# GSMLiftSquare.net
KiCad netlist of a schematic drawn in Altium Designer
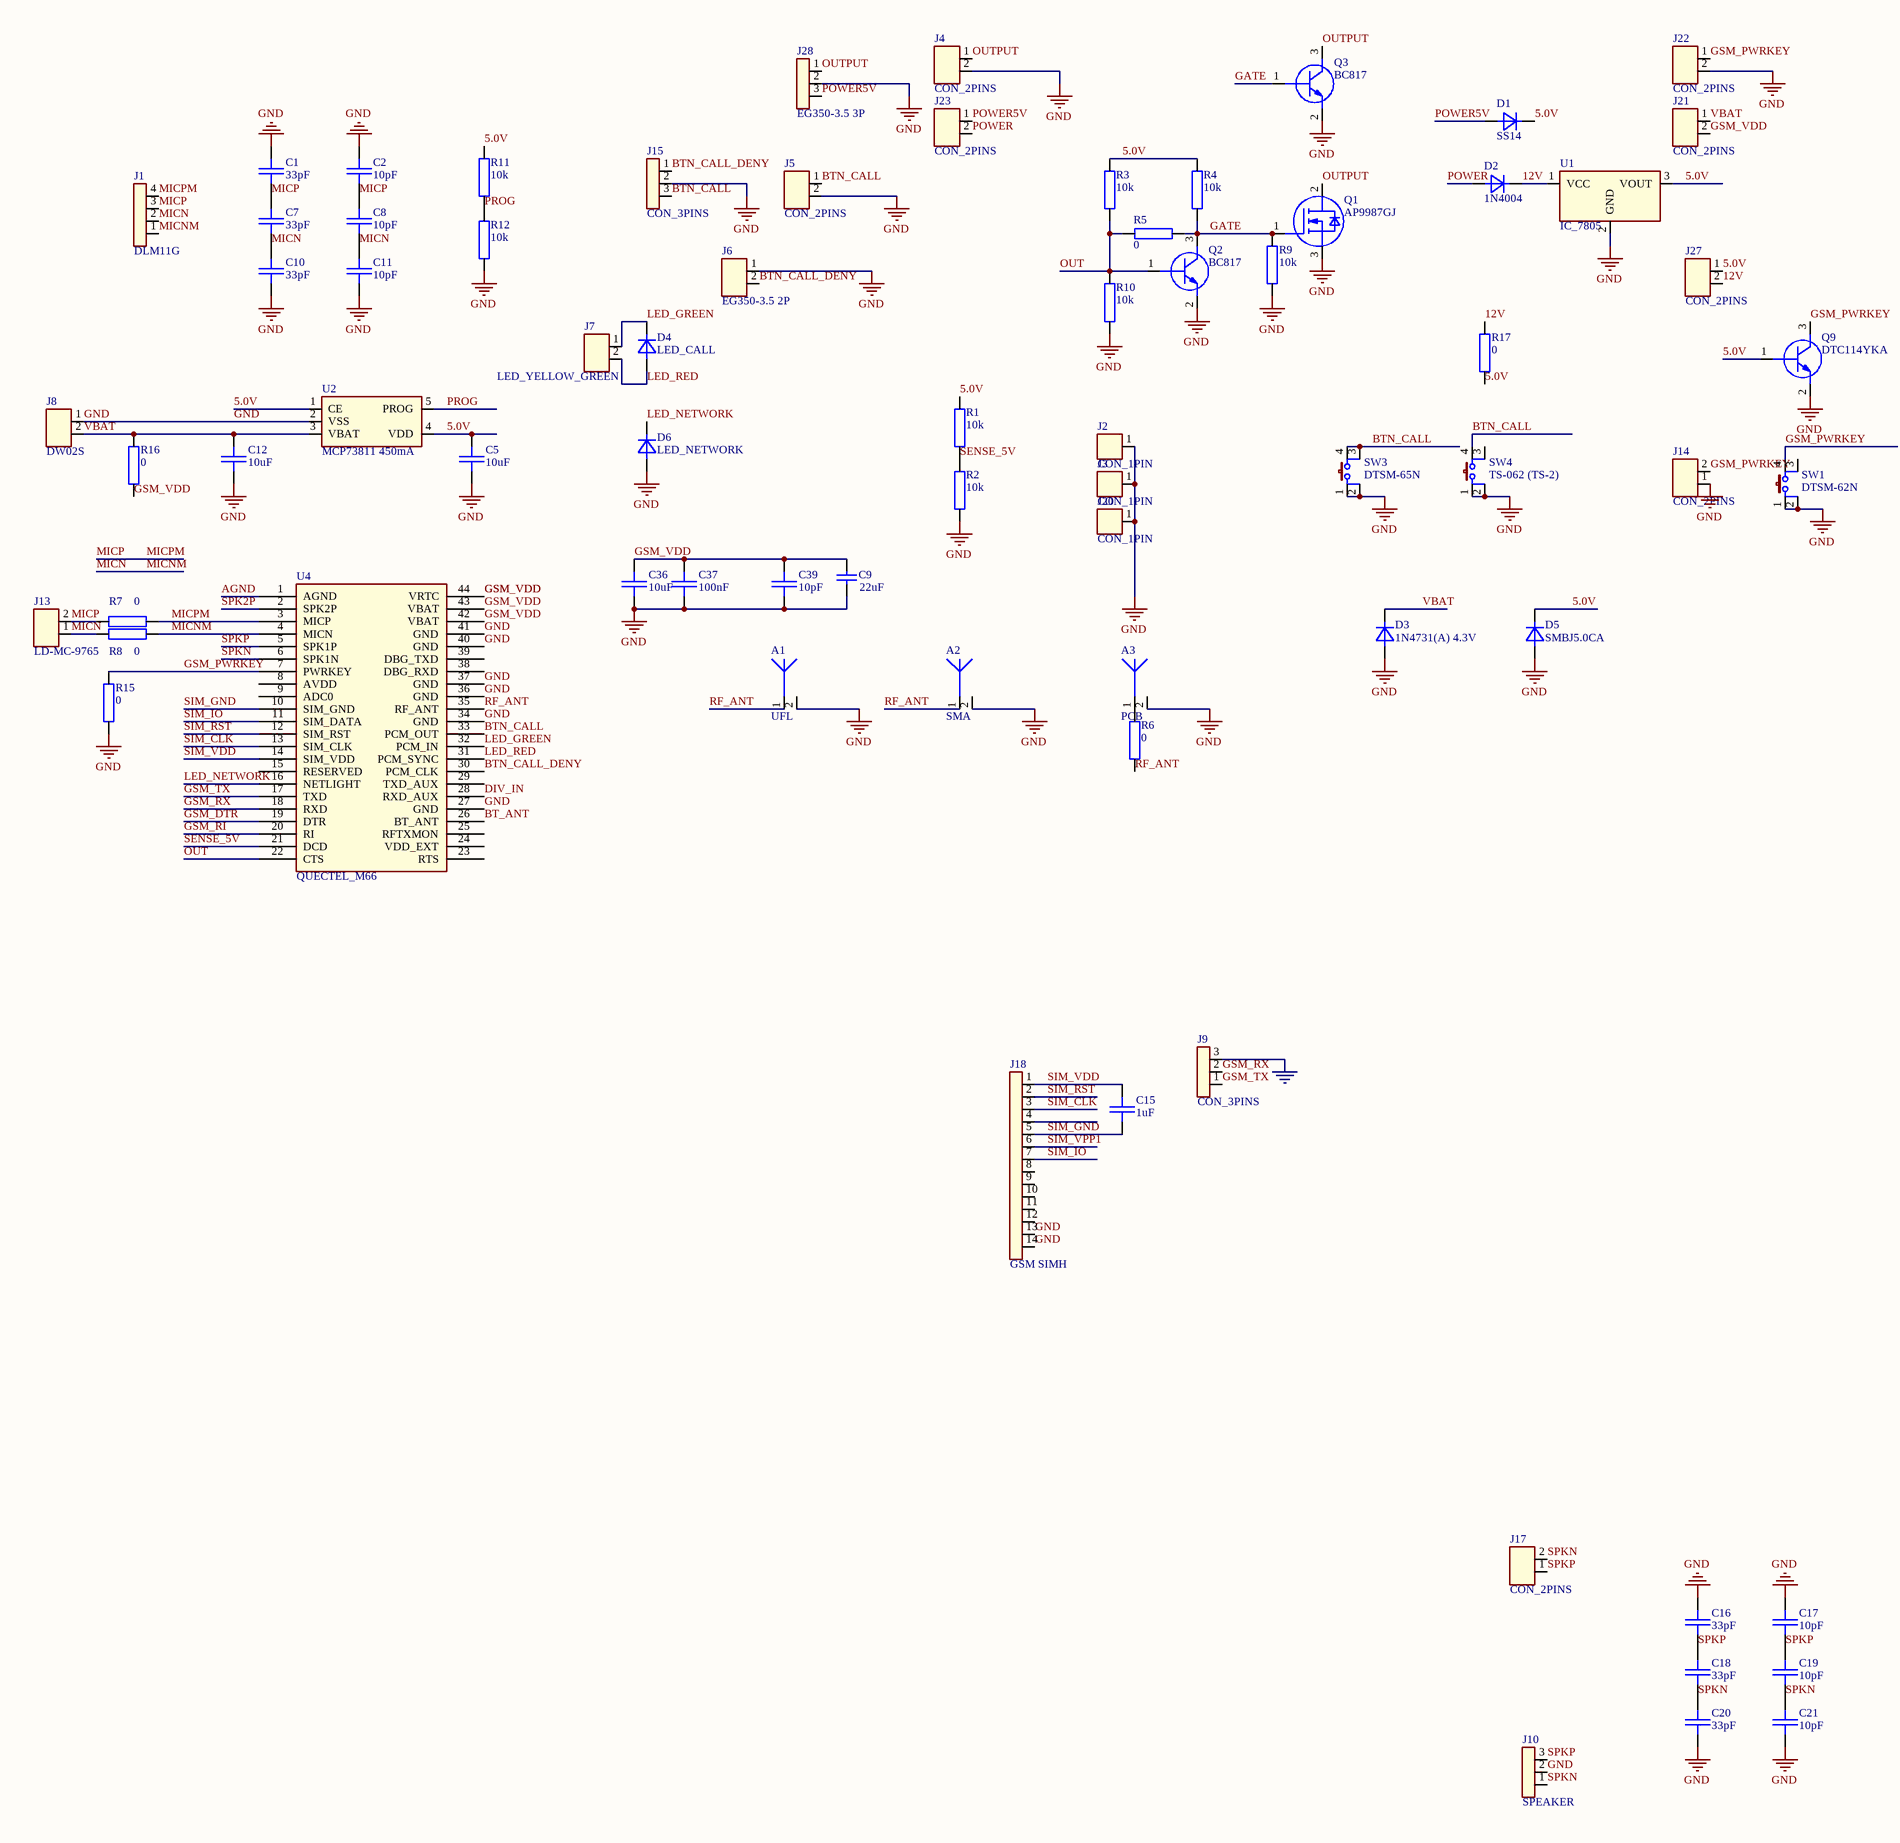
[diagram p0: GSMLiftSquare.SchDoc, left]
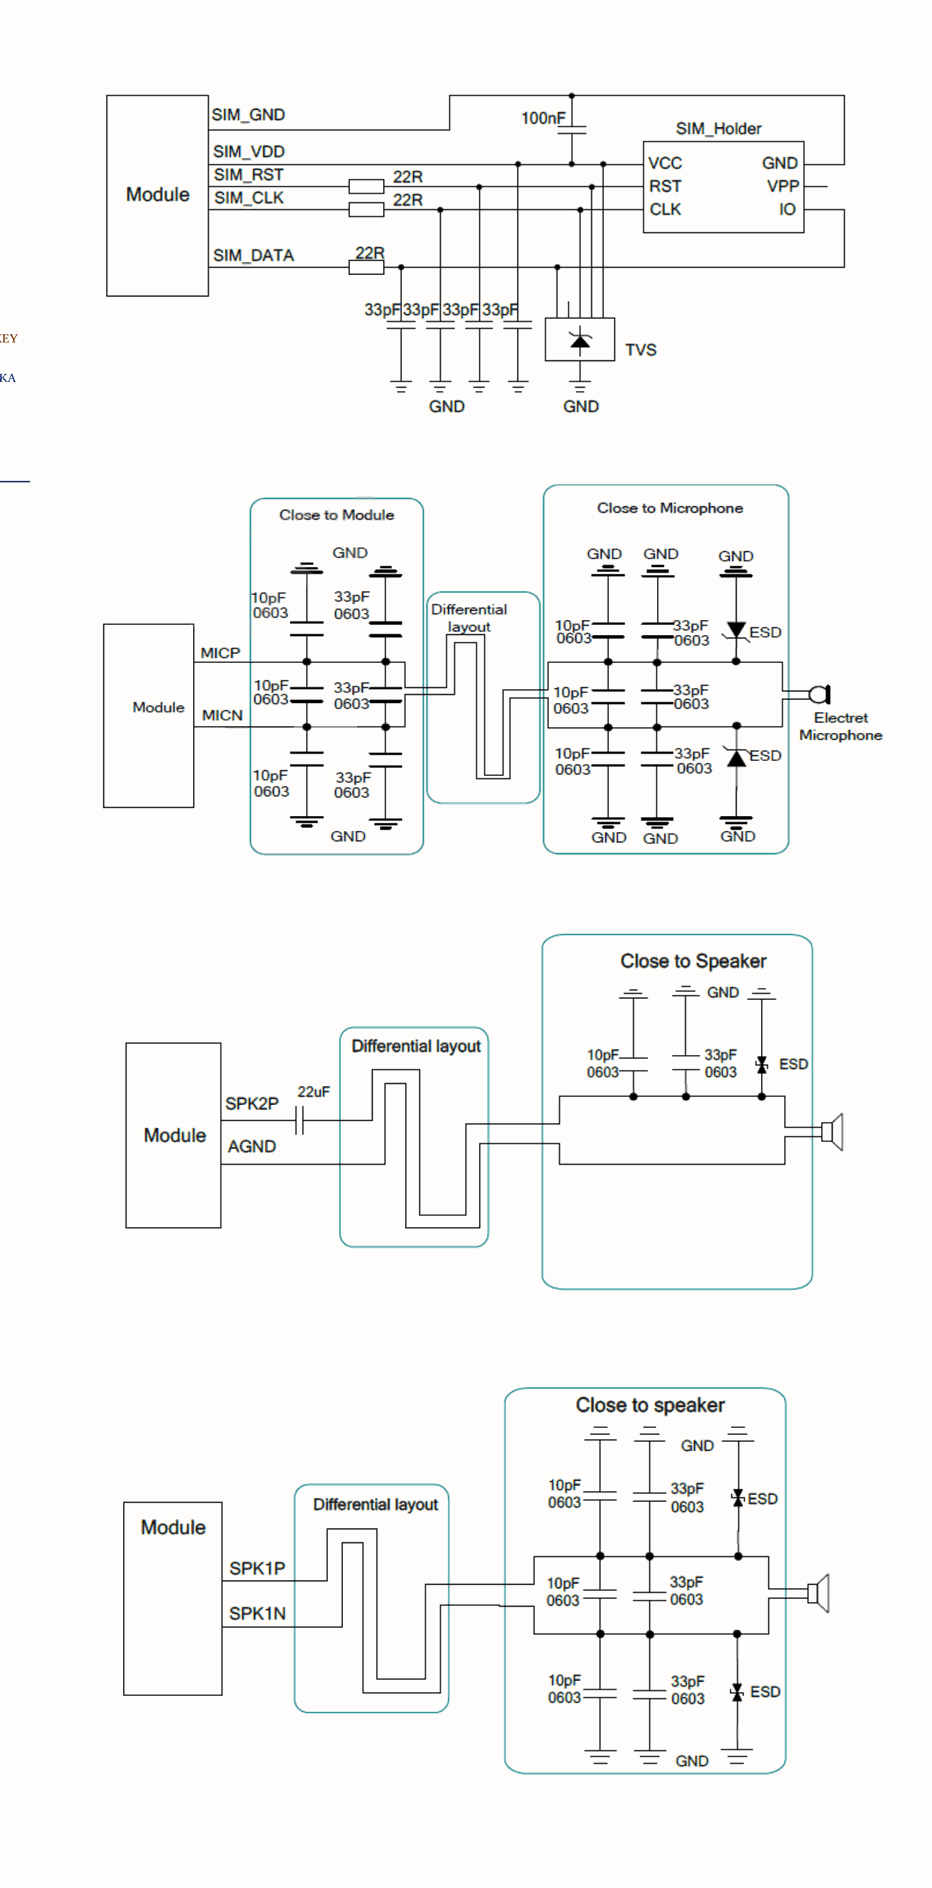
[diagram p1: GSMLiftSquare.SchDoc, right]

(export (version "E")
  (design (tool "Eeschema 10.0.6"))
  (components
    (comp (ref "A1")
      (value "UFL")
      (footprint "SMD_CON_ANTENNA_UFL")
      (libsource (lib "DLV") (part "ANTENNA_2"))
    )
    (comp (ref "A2")
      (value "SMA")
      (footprint "SMD_CON_ANTENNA_SMA_RIGHT_ANGLE")
      (libsource (lib "DLV") (part "ANTENNA_2"))
    )
    (comp (ref "A3")
      (value "PCB")
      (footprint "SMD_CON_ANTENNA_GSM_PCB_1")
      (libsource (lib "DLV") (part "ANTENNA_2"))
    )
    (comp (ref "C1") (value "33pF") (footprint "SMD_0603_CAPC1608X95N") (libsource (lib "DLV") (part "C")))
    (comp (ref "C2") (value "10pF") (footprint "SMD_0603_CAPC1608X95N") (libsource (lib "DLV") (part "C")))
    (comp (ref "C5") (value "10uF") (footprint "SMD_0603_CAPC1608X95N") (libsource (lib "DLV") (part "C")))
    (comp (ref "C7") (value "33pF") (footprint "SMD_0603_CAPC1608X95N") (libsource (lib "DLV") (part "C")))
    (comp (ref "C8") (value "10pF") (footprint "SMD_0603_CAPC1608X95N") (libsource (lib "DLV") (part "C")))
    (comp (ref "C9")
      (value "22uF")
      (footprint "SMD_1210_CAPC3225X279N")
      (description "CL32A227MQVNNNE 220UF 6.3V 20% X5R 1210")
      (fields (field (name "PUBLISHER") "Altium Limited"))
      (libsource (lib "Miscellaneous Devices") (part "Cap Semi"))
    )
    (comp (ref "C10") (value "33pF") (footprint "SMD_0603_CAPC1608X95N") (libsource (lib "DLV") (part "C")))
    (comp (ref "C11") (value "10pF") (footprint "SMD_0603_CAPC1608X95N") (libsource (lib "DLV") (part "C")))
    (comp (ref "C12") (value "10uF") (footprint "SMD_0603_CAPC1608X95N") (libsource (lib "DLV") (part "C")))
    (comp (ref "C15") (value "1uF") (footprint "SMD_0603_CAPC1608X95N") (libsource (lib "DLV") (part "C")))
    (comp (ref "C16") (value "33pF") (footprint "SMD_0603_CAPC1608X95N") (libsource (lib "DLV") (part "C")))
    (comp (ref "C17") (value "10pF") (footprint "SMD_0603_CAPC1608X95N") (libsource (lib "DLV") (part "C")))
    (comp (ref "C18") (value "33pF") (footprint "SMD_0603_CAPC1608X95N") (libsource (lib "DLV") (part "C")))
    (comp (ref "C19") (value "10pF") (footprint "SMD_0603_CAPC1608X95N") (libsource (lib "DLV") (part "C")))
    (comp (ref "C20") (value "33pF") (footprint "SMD_0603_CAPC1608X95N") (libsource (lib "DLV") (part "C")))
    (comp (ref "C21") (value "10pF") (footprint "SMD_0603_CAPC1608X95N") (libsource (lib "DLV") (part "C")))
    (comp (ref "C36") (value "10uF") (footprint "SMD_0805_CAPC2012X95N") (libsource (lib "DLV") (part "C")))
    (comp (ref "C37") (value "100nF") (footprint "SMD_0603_CAPC1608X95N") (libsource (lib "DLV") (part "C")))
    (comp (ref "C39") (value "10pF") (footprint "SMD_0603_CAPC1608X95N") (libsource (lib "DLV") (part "C")))
    (comp (ref "D1")
      (value "SS14")
      (footprint "SMD_DO214AC_SMA")
      (libsource (lib "EPIQ_DND_CIS_Library") (part "D"))
    )
    (comp (ref "D2")
      (value "1N4004")
      (footprint "SMD_DO214AC_SMA")
      (libsource (lib "EPIQ_DND_CIS_Library") (part "D"))
    )
    (comp (ref "D3")
      (value "1N4731(A) 4.3V")
      (footprint "PTH_HDRV02W64P254_1X02")
      (libsource (lib "EPIQ_DND_CIS_Library") (part "D"))
    )
    (comp (ref "D4")
      (value "LED_CALL")
      (footprint "SMD_0805_LED2012X100N")
      (libsource (lib "DLV") (part "D"))
    )
    (comp (ref "D5")
      (value "SMBJ5.0CA")
      (footprint "SMD_DO214AC_SMB")
      (libsource (lib "EPIQ_DND_CIS_Library") (part "D"))
    )
    (comp (ref "D6")
      (value "LED_NETWORK")
      (footprint "SMD_0805_LED2012X100N")
      (libsource (lib "DLV") (part "D"))
    )
    (comp (ref "J1")
      (value "DLM11G")
      (footprint "SMD_COMMON_MODE_CHOKE")
      (libsource (lib "DLV") (part "CON_4PINS"))
    )
    (comp (ref "J2")
      (value "CON_1PIN")
      (footprint "PTH_MOUNT_HOLE")
      (libsource (lib "DLV") (part "CON_1PIN"))
    )
    (comp (ref "J3")
      (value "CON_1PIN")
      (footprint "PTH_MOUNT_HOLE")
      (libsource (lib "DLV") (part "CON_1PIN"))
    )
    (comp (ref "J4")
      (value "CON_2PINS")
      (footprint "PTH_HDRV02W11060P350_1X02")
      (libsource (lib "DLV") (part "CON_2PINS"))
    )
    (comp (ref "J5")
      (value "CON_2PINS")
      (footprint "PTH_HDRV02W11060P500_1X02")
      (libsource (lib "DLV") (part "CON_2PINS"))
    )
    (comp (ref "J6")
      (value "EG350-3.5 2P")
      (footprint "PTH_HDRV02W11060P350_1X02")
      (libsource (lib "DLV") (part "CON_2PINS"))
    )
    (comp (ref "J7")
      (value "LED_YELLOW_GREEN")
      (footprint "PTH_LED-KINGBRIGHT-L-934SGC")
      (libsource (lib "DLV") (part "CON_2PINS"))
    )
    (comp (ref "J8")
      (value "DW02S")
      (footprint "PTH_HDRV02W64P254_1X02_BATTERY")
      (libsource (lib "DLV") (part "CON_2PINS"))
    )
    (comp (ref "J9")
      (value "CON_3PINS")
      (footprint "PTH_HDRV03W64P254_1X03")
      (libsource (lib "") (part "CON_3PINS_1"))
    )
    (comp (ref "J10")
      (value "SPEAKER")
      (footprint "PTH_SPEAKER_MCABS-227-RC")
      (libsource (lib "") (part "CON_3PINS_1"))
    )
    (comp (ref "J13")
      (value "LD-MC-9765")
      (footprint "PTH_MIC_9.6MM_6MM")
      (libsource (lib "") (part "CON_2PINS_1"))
    )
    (comp (ref "J14")
      (value "CON_2PINS")
      (footprint "PTH_HDRV02W64P254_1X02")
      (libsource (lib "") (part "CON_2PINS_1"))
    )
    (comp (ref "J15")
      (value "CON_3PINS")
      (footprint "PTH_HDRV03W64P254_1X03")
      (libsource (lib "DLV") (part "CON_3PINS"))
    )
    (comp (ref "J17")
      (value "CON_2PINS")
      (footprint "PTH_HDRV02W64P254_1X02")
      (libsource (lib "") (part "CON_2PINS_1"))
    )
    (comp (ref "J18")
      (value "GSM SIMH")
      (footprint "SMD_CON-ATTEND_SIM_115B-AAA0-R01")
      (libsource (lib "DLV") (part "CON_14PINS"))
    )
    (comp (ref "J20")
      (value "CON_1PIN")
      (footprint "PTH_MOUNT_HOLE")
      (libsource (lib "DLV") (part "CON_1PIN"))
    )
    (comp (ref "J21")
      (value "CON_2PINS")
      (footprint "PTH_HDRV02W64P254_1X02")
      (libsource (lib "DLV") (part "CON_2PINS"))
    )
    (comp (ref "J22")
      (value "CON_2PINS")
      (footprint "PTH_HDRV02W64P254_1X02")
      (libsource (lib "DLV") (part "CON_2PINS"))
    )
    (comp (ref "J23")
      (value "CON_2PINS")
      (footprint "PTH_HDRV02W11060P350_1X02")
      (libsource (lib "DLV") (part "CON_2PINS"))
    )
    (comp (ref "J27")
      (value "CON_2PINS")
      (footprint "PTH_HDRV02W64P254_1X02")
      (libsource (lib "DLV") (part "CON_2PINS"))
    )
    (comp (ref "J28")
      (value "EG350-3.5 3P")
      (footprint "PTH_HDRV02W11060P350_1X03")
      (libsource (lib "DLV") (part "CON_3PINS"))
    )
    (comp (ref "Q1")
      (value "AP9987GJ")
      (footprint "PTH_TO220AB")
      (libsource (lib "DLV") (part "MOS_N_D1_G1D2S3"))
    )
    (comp (ref "Q2")
      (value "BC817")
      (footprint "SMD_SOT23_SOT95P240X120-3N")
      (libsource (lib "DLV") (part "BJT_NPN_B1E2C3"))
    )
    (comp (ref "Q3")
      (value "BC817")
      (footprint "SMD_SOT23_SOT95P240X120-3N")
      (libsource (lib "DLV") (part "BJT_NPN_B1E2C3"))
    )
    (comp (ref "Q9")
      (value "DTC114YKA")
      (footprint "SMD_SOT23_SOT95P240X120-3N")
      (libsource (lib "DLV") (part "BJT_NPN_B1E2C3"))
    )
    (comp (ref "R1") (value "10k") (footprint "SMD_0603_RESC1608X55N") (libsource (lib "DLV") (part "R")))
    (comp (ref "R2") (value "10k") (footprint "SMD_0603_RESC1608X55N") (libsource (lib "DLV") (part "R")))
    (comp (ref "R3") (value "10k") (footprint "SMD_0603_RESC1608X55N") (libsource (lib "DLV") (part "R")))
    (comp (ref "R4") (value "10k") (footprint "SMD_0603_RESC1608X55N") (libsource (lib "DLV") (part "R")))
    (comp (ref "R5") (value "0") (footprint "SMD_0603_RESC1608X55N") (libsource (lib "DLV") (part "R")))
    (comp (ref "R6") (value "0") (footprint "SMD_0402_RESC1005X37N") (libsource (lib "DLV") (part "R")))
    (comp (ref "R7") (value "0") (footprint "SMD_0402_RESC1005X37N") (libsource (lib "DLV") (part "R")))
    (comp (ref "R8") (value "0") (footprint "SMD_0402_RESC1005X37N") (libsource (lib "DLV") (part "R")))
    (comp (ref "R9") (value "10k") (footprint "SMD_0603_RESC1608X55N") (libsource (lib "DLV") (part "R")))
    (comp (ref "R10") (value "10k") (footprint "SMD_0603_RESC1608X55N") (libsource (lib "DLV") (part "R")))
    (comp (ref "R11") (value "10k") (footprint "SMD_0603_RESC1608X55N") (libsource (lib "DLV") (part "R")))
    (comp (ref "R12") (value "10k") (footprint "SMD_0603_RESC1608X55N") (libsource (lib "DLV") (part "R")))
    (comp (ref "R15") (value "0") (footprint "SMD_0603_RESC1608X55N") (libsource (lib "DLV") (part "R")))
    (comp (ref "R16") (value "0") (footprint "SMD_0603_RESC1608X55N") (libsource (lib "DLV") (part "R")))
    (comp (ref "R17") (value "0") (footprint "SMD_0603_RESC1608X55N") (libsource (lib "DLV") (part "R")))
    (comp (ref "SW1")
      (value "DTSM-62N")
      (footprint "SMD_SW_TACT-64K_5")
      (libsource (lib "DLV") (part "BUTTON_1"))
    )
    (comp (ref "SW3")
      (value "DTSM-65N")
      (footprint "SMD_SW_TACT-64K_5")
      (libsource (lib "DLV") (part "BUTTON_1"))
    )
    (comp (ref "SW4")
      (value "TS-062 (TS-2)")
      (footprint "PTH_SWI_TACT-62K_5")
      (libsource (lib "DLV") (part "BUTTON_1"))
    )
    (comp (ref "U1") (value "IC_7805") (footprint "PTH_TO220AB") (libsource (lib "DLV") (part "IC_7805")))
    (comp (ref "U2")
      (value "MCP73811 450mA")
      (footprint "SMD_SOT26_SOT95P285X140-5N - DLV")
      (description "MCP73812")
      (fields
        (field (name "DB_PART_NUMBER") "PSU000000127")
        (field (name "DB_MANUFACTURER_PART") "ROHM        BD33KA5WF-E2")
        (field (name "DB_APPROVED_BY") "VSN")
      )
      (libsource (lib "DLV") (part "IC_MCP73812"))
    )
    (comp (ref "U4")
      (value "QUECTEL_M66")
      (footprint "SMD_MOD_M66-44N")
      (libsource (lib "DLV") (part "MOD_QUECTEL_M66"))
    )
  )
  (nets
    (net (code "1") (name "/5.0V") (class "Default")
      (node (ref "C5") (pin "1") (pinfunction "1_1") (pintype "passive"))
      (node (ref "D1") (pin "1") (pinfunction "C_1") (pintype "passive"))
      (node (ref "D5") (pin "1") (pinfunction "C_1") (pintype "passive"))
      (node (ref "J27") (pin "1") (pinfunction "1_1") (pintype "passive"))
      (node (ref "Q9") (pin "1") (pinfunction "B_1") (pintype "passive"))
      (node (ref "R1") (pin "1") (pinfunction "1_1") (pintype "passive"))
      (node (ref "R11") (pin "1") (pinfunction "1_1") (pintype "passive"))
      (node (ref "R17") (pin "2") (pinfunction "2_2") (pintype "passive"))
      (node (ref "R3") (pin "1") (pinfunction "1_1") (pintype "passive"))
      (node (ref "R4") (pin "1") (pinfunction "1_1") (pintype "passive"))
      (node (ref "U1") (pin "3") (pinfunction "VOUT_3") (pintype "passive"))
      (node (ref "U2") (pin "1") (pinfunction "CE_1") (pintype "passive"))
      (node (ref "U2") (pin "4") (pinfunction "VDD_4") (pintype "passive"))
    )
    (net (code "2") (name "/12V") (class "Default")
      (node (ref "D2") (pin "1") (pinfunction "C_1") (pintype "passive"))
      (node (ref "J27") (pin "2") (pinfunction "2_2") (pintype "passive"))
      (node (ref "R17") (pin "1") (pinfunction "1_1") (pintype "passive"))
      (node (ref "U1") (pin "1") (pinfunction "VCC_1") (pintype "passive"))
    )
    (net (code "3") (name "/AGND") (class "Default")
      (node (ref "U4") (pin "1") (pinfunction "AGND_1") (pintype "passive"))
    )
    (net (code "4") (name "/BTN_CALL") (class "Default")
      (node (ref "J15") (pin "3") (pinfunction "3_3") (pintype "passive"))
      (node (ref "J5") (pin "1") (pinfunction "1_1") (pintype "passive"))
      (node (ref "SW3") (pin "3") (pinfunction "3_3") (pintype "passive"))
      (node (ref "SW3") (pin "4") (pinfunction "4_4") (pintype "passive"))
      (node (ref "SW4") (pin "4") (pinfunction "4_4") (pintype "passive"))
      (node (ref "U4") (pin "33") (pinfunction "PCM_OUT_33") (pintype "passive"))
    )
    (net (code "5") (name "/BTN_CALL_DENY") (class "Default")
      (node (ref "J15") (pin "1") (pinfunction "1_1") (pintype "passive"))
      (node (ref "J6") (pin "2") (pinfunction "2_2") (pintype "passive"))
      (node (ref "U4") (pin "30") (pinfunction "PCM_CLK_30") (pintype "passive"))
    )
    (net (code "6") (name "/BT_ANT") (class "Default")
      (node (ref "U4") (pin "26") (pinfunction "BT_ANT_26") (pintype "passive"))
    )
    (net (code "7") (name "/DIV_IN") (class "Default")
      (node (ref "U4") (pin "28") (pinfunction "RXD_AUX_28") (pintype "passive"))
    )
    (net (code "8") (name "/GATE") (class "Default")
      (node (ref "Q1") (pin "1") (pinfunction "G_1") (pintype "passive"))
      (node (ref "Q2") (pin "3") (pinfunction "C_3") (pintype "passive"))
      (node (ref "Q3") (pin "1") (pinfunction "B_1") (pintype "passive"))
      (node (ref "R4") (pin "2") (pinfunction "2_2") (pintype "passive"))
      (node (ref "R5") (pin "2") (pinfunction "2_2") (pintype "passive"))
      (node (ref "R9") (pin "1") (pinfunction "1_1") (pintype "passive"))
    )
    (net (code "9") (name "/GSM_DTR") (class "Default")
      (node (ref "U4") (pin "19") (pinfunction "DTR_19") (pintype "passive"))
    )
    (net (code "10") (name "/GSM_PWRKEY") (class "Default")
      (node (ref "J14") (pin "2") (pinfunction "2_2") (pintype "passive"))
      (node (ref "J22") (pin "1") (pinfunction "1_1") (pintype "passive"))
      (node (ref "Q9") (pin "3") (pinfunction "C_3") (pintype "passive"))
      (node (ref "R15") (pin "1") (pinfunction "1_1") (pintype "passive"))
      (node (ref "SW1") (pin "4") (pinfunction "4_4") (pintype "passive"))
      (node (ref "U4") (pin "7") (pinfunction "PWRKEY_7") (pintype "passive"))
    )
    (net (code "11") (name "/GSM_RI") (class "Default")
      (node (ref "U4") (pin "20") (pinfunction "RI_20") (pintype "passive"))
    )
    (net (code "12") (name "/GSM_RX") (class "Default")
      (node (ref "J9") (pin "2") (pinfunction "2_2") (pintype "passive"))
      (node (ref "U4") (pin "18") (pinfunction "RXD_18") (pintype "passive"))
    )
    (net (code "13") (name "/GSM_TX") (class "Default")
      (node (ref "J9") (pin "1") (pinfunction "1_1") (pintype "passive"))
      (node (ref "U4") (pin "17") (pinfunction "TXD_17") (pintype "passive"))
    )
    (net (code "14") (name "/GSM_VDD") (class "Default")
      (node (ref "C36") (pin "1") (pinfunction "1_1") (pintype "passive"))
      (node (ref "C37") (pin "1") (pinfunction "1_1") (pintype "passive"))
      (node (ref "C39") (pin "1") (pinfunction "1_1") (pintype "passive"))
      (node (ref "C9") (pin "1") (pinfunction "1_1") (pintype "passive"))
      (node (ref "J21") (pin "2") (pinfunction "2_2") (pintype "passive"))
      (node (ref "R16") (pin "1") (pinfunction "1_1") (pintype "passive"))
      (node (ref "U4") (pin "42") (pinfunction "VBAT_42") (pintype "passive"))
      (node (ref "U4") (pin "43") (pinfunction "VBAT_43") (pintype "passive"))
      (node (ref "U4") (pin "44") (pinfunction "VRTC_44") (pintype "passive"))
    )
    (net (code "15") (name "/LED_GREEN") (class "Default")
      (node (ref "D4") (pin "1") (pinfunction "C_1") (pintype "passive"))
      (node (ref "J7") (pin "1") (pinfunction "1_1") (pintype "passive"))
      (node (ref "U4") (pin "32") (pinfunction "PCM_IN_32") (pintype "passive"))
    )
    (net (code "16") (name "/LED_NETWORK") (class "Default")
      (node (ref "D6") (pin "1") (pinfunction "C_1") (pintype "passive"))
      (node (ref "U4") (pin "16") (pinfunction "NETLIGHT_16") (pintype "passive"))
    )
    (net (code "17") (name "/LED_RED") (class "Default")
      (node (ref "D4") (pin "2") (pinfunction "A_2") (pintype "passive"))
      (node (ref "J7") (pin "2") (pinfunction "2_2") (pintype "passive"))
      (node (ref "U4") (pin "31") (pinfunction "PCM_SYNC_31") (pintype "passive"))
    )
    (net (code "18") (name "/MICN") (class "Default")
      (node (ref "C10") (pin "1") (pinfunction "1_1") (pintype "passive"))
      (node (ref "C11") (pin "1") (pinfunction "1_1") (pintype "passive"))
      (node (ref "C7") (pin "2") (pinfunction "2_2") (pintype "passive"))
      (node (ref "C8") (pin "2") (pinfunction "2_2") (pintype "passive"))
      (node (ref "J1") (pin "1") (pinfunction "1_1") (pintype "passive"))
      (node (ref "J1") (pin "2") (pinfunction "2_2") (pintype "passive"))
      (node (ref "J13") (pin "1") (pinfunction "1_1") (pintype "passive"))
      (node (ref "R8") (pin "1") (pinfunction "1_1") (pintype "passive"))
      (node (ref "R8") (pin "2") (pinfunction "2_2") (pintype "passive"))
      (node (ref "U4") (pin "4") (pinfunction "MICN_4") (pintype "passive"))
    )
    (net (code "19") (name "/MICP") (class "Default")
      (node (ref "C1") (pin "2") (pinfunction "2_2") (pintype "passive"))
      (node (ref "C2") (pin "2") (pinfunction "2_2") (pintype "passive"))
      (node (ref "C7") (pin "1") (pinfunction "1_1") (pintype "passive"))
      (node (ref "C8") (pin "1") (pinfunction "1_1") (pintype "passive"))
      (node (ref "J1") (pin "3") (pinfunction "3_3") (pintype "passive"))
      (node (ref "J1") (pin "4") (pinfunction "4_4") (pintype "passive"))
      (node (ref "J13") (pin "2") (pinfunction "2_2") (pintype "passive"))
      (node (ref "R7") (pin "1") (pinfunction "1_1") (pintype "passive"))
      (node (ref "R7") (pin "2") (pinfunction "2_2") (pintype "passive"))
      (node (ref "U4") (pin "3") (pinfunction "MICP_3") (pintype "passive"))
    )
    (net (code "20") (name "/OUT") (class "Default")
      (node (ref "Q2") (pin "1") (pinfunction "B_1") (pintype "passive"))
      (node (ref "R10") (pin "1") (pinfunction "1_1") (pintype "passive"))
      (node (ref "R3") (pin "2") (pinfunction "2_2") (pintype "passive"))
      (node (ref "R5") (pin "1") (pinfunction "1_1") (pintype "passive"))
      (node (ref "U4") (pin "22") (pinfunction "CTS_22") (pintype "passive"))
    )
    (net (code "21") (name "/OUTPUT") (class "Default")
      (node (ref "J28") (pin "1") (pinfunction "1_1") (pintype "passive"))
      (node (ref "J4") (pin "1") (pinfunction "1_1") (pintype "passive"))
      (node (ref "Q1") (pin "2") (pinfunction "D_2") (pintype "passive"))
      (node (ref "Q3") (pin "3") (pinfunction "C_3") (pintype "passive"))
    )
    (net (code "22") (name "/POWER") (class "Default")
      (node (ref "D2") (pin "2") (pinfunction "A_2") (pintype "passive"))
      (node (ref "J23") (pin "2") (pinfunction "2_2") (pintype "passive"))
    )
    (net (code "23") (name "/POWER5V") (class "Default")
      (node (ref "D1") (pin "2") (pinfunction "A_2") (pintype "passive"))
      (node (ref "J23") (pin "1") (pinfunction "1_1") (pintype "passive"))
      (node (ref "J28") (pin "3") (pinfunction "3_3") (pintype "passive"))
    )
    (net (code "24") (name "/PROG") (class "Default")
      (node (ref "R11") (pin "2") (pinfunction "2_2") (pintype "passive"))
      (node (ref "R12") (pin "1") (pinfunction "1_1") (pintype "passive"))
      (node (ref "U2") (pin "5") (pinfunction "PROG_5") (pintype "passive"))
    )
    (net (code "25") (name "/RF_ANT") (class "Default")
      (node (ref "A1") (pin "1") (pinfunction "1_1") (pintype "passive"))
      (node (ref "A2") (pin "1") (pinfunction "1_1") (pintype "passive"))
      (node (ref "R6") (pin "2") (pinfunction "2_2") (pintype "passive"))
      (node (ref "U4") (pin "35") (pinfunction "RF_ANT_35") (pintype "passive"))
    )
    (net (code "26") (name "/SENSE_5V") (class "Default")
      (node (ref "R1") (pin "2") (pinfunction "2_2") (pintype "passive"))
      (node (ref "R2") (pin "1") (pinfunction "1_1") (pintype "passive"))
      (node (ref "U4") (pin "21") (pinfunction "DCD_21") (pintype "passive"))
    )
    (net (code "27") (name "/SIM_CLK") (class "Default")
      (node (ref "J18") (pin "3") (pinfunction "3_3") (pintype "passive"))
      (node (ref "U4") (pin "13") (pinfunction "SIM_CLK_13") (pintype "passive"))
    )
    (net (code "28") (name "/SIM_GND") (class "Default")
      (node (ref "C15") (pin "2") (pinfunction "2_2") (pintype "passive"))
      (node (ref "J18") (pin "5") (pinfunction "5_5") (pintype "passive"))
      (node (ref "U4") (pin "10") (pinfunction "SIM_GND_10") (pintype "passive"))
    )
    (net (code "29") (name "/SIM_IO") (class "Default")
      (node (ref "J18") (pin "7") (pinfunction "7_7") (pintype "passive"))
      (node (ref "U4") (pin "11") (pinfunction "SIM_DATA_11") (pintype "passive"))
    )
    (net (code "30") (name "/SIM_RST") (class "Default")
      (node (ref "J18") (pin "2") (pinfunction "2_2") (pintype "passive"))
      (node (ref "U4") (pin "12") (pinfunction "SIM_RST_12") (pintype "passive"))
    )
    (net (code "31") (name "/SIM_VDD") (class "Default")
      (node (ref "C15") (pin "1") (pinfunction "1_1") (pintype "passive"))
      (node (ref "J18") (pin "1") (pinfunction "1_1") (pintype "passive"))
      (node (ref "U4") (pin "14") (pinfunction "SIM_VDD_14") (pintype "passive"))
    )
    (net (code "32") (name "/SIM_VPP1") (class "Default")
      (node (ref "J18") (pin "6") (pinfunction "6_6") (pintype "passive"))
    )
    (net (code "33") (name "/SPK2P") (class "Default")
      (node (ref "U4") (pin "2") (pinfunction "SPK2P_2") (pintype "passive"))
    )
    (net (code "34") (name "/SPKN") (class "Default")
      (node (ref "C18") (pin "2") (pinfunction "2_2") (pintype "passive"))
      (node (ref "C19") (pin "2") (pinfunction "2_2") (pintype "passive"))
      (node (ref "C20") (pin "1") (pinfunction "1_1") (pintype "passive"))
      (node (ref "C21") (pin "1") (pinfunction "1_1") (pintype "passive"))
      (node (ref "J10") (pin "1") (pinfunction "1_1") (pintype "passive"))
      (node (ref "J17") (pin "2") (pinfunction "2_2") (pintype "passive"))
      (node (ref "U4") (pin "6") (pinfunction "SPK1N_6") (pintype "passive"))
    )
    (net (code "35") (name "/SPKP") (class "Default")
      (node (ref "C16") (pin "2") (pinfunction "2_2") (pintype "passive"))
      (node (ref "C17") (pin "2") (pinfunction "2_2") (pintype "passive"))
      (node (ref "C18") (pin "1") (pinfunction "1_1") (pintype "passive"))
      (node (ref "C19") (pin "1") (pinfunction "1_1") (pintype "passive"))
      (node (ref "J10") (pin "3") (pinfunction "3_3") (pintype "passive"))
      (node (ref "J17") (pin "1") (pinfunction "1_1") (pintype "passive"))
      (node (ref "U4") (pin "5") (pinfunction "SPK1P_5") (pintype "passive"))
    )
    (net (code "36") (name "/VBAT") (class "Default")
      (node (ref "C12") (pin "1") (pinfunction "1_1") (pintype "passive"))
      (node (ref "D3") (pin "1") (pinfunction "C_1") (pintype "passive"))
      (node (ref "J21") (pin "1") (pinfunction "1_1") (pintype "passive"))
      (node (ref "J8") (pin "2") (pinfunction "2_2") (pintype "passive"))
      (node (ref "R16") (pin "2") (pinfunction "2_2") (pintype "passive"))
      (node (ref "U2") (pin "3") (pinfunction "VBAT_3") (pintype "passive"))
    )
    (net (code "37") (name "GND") (class "Default")
      (node (ref "A1") (pin "2") (pinfunction "2_2") (pintype "passive"))
      (node (ref "A2") (pin "2") (pinfunction "2_2") (pintype "passive"))
      (node (ref "A3") (pin "2") (pinfunction "2_2") (pintype "passive"))
      (node (ref "C1") (pin "1") (pinfunction "1_1") (pintype "passive"))
      (node (ref "C10") (pin "2") (pinfunction "2_2") (pintype "passive"))
      (node (ref "C11") (pin "2") (pinfunction "2_2") (pintype "passive"))
      (node (ref "C12") (pin "2") (pinfunction "2_2") (pintype "passive"))
      (node (ref "C16") (pin "1") (pinfunction "1_1") (pintype "passive"))
      (node (ref "C17") (pin "1") (pinfunction "1_1") (pintype "passive"))
      (node (ref "C2") (pin "1") (pinfunction "1_1") (pintype "passive"))
      (node (ref "C20") (pin "2") (pinfunction "2_2") (pintype "passive"))
      (node (ref "C21") (pin "2") (pinfunction "2_2") (pintype "passive"))
      (node (ref "C36") (pin "2") (pinfunction "2_2") (pintype "passive"))
      (node (ref "C37") (pin "2") (pinfunction "2_2") (pintype "passive"))
      (node (ref "C39") (pin "2") (pinfunction "2_2") (pintype "passive"))
      (node (ref "C5") (pin "2") (pinfunction "2_2") (pintype "passive"))
      (node (ref "C9") (pin "2") (pinfunction "2_2") (pintype "passive"))
      (node (ref "D3") (pin "2") (pinfunction "A_2") (pintype "passive"))
      (node (ref "D5") (pin "2") (pinfunction "A_2") (pintype "passive"))
      (node (ref "D6") (pin "2") (pinfunction "A_2") (pintype "passive"))
      (node (ref "J10") (pin "2") (pinfunction "2_2") (pintype "passive"))
      (node (ref "J14") (pin "1") (pinfunction "1_1") (pintype "passive"))
      (node (ref "J15") (pin "2") (pinfunction "2_2") (pintype "passive"))
      (node (ref "J18") (pin "13") (pinfunction "13_13") (pintype "passive"))
      (node (ref "J18") (pin "14") (pinfunction "14_14") (pintype "passive"))
      (node (ref "J2") (pin "1") (pinfunction "1_1") (pintype "passive"))
      (node (ref "J20") (pin "1") (pinfunction "1_1") (pintype "passive"))
      (node (ref "J22") (pin "2") (pinfunction "2_2") (pintype "passive"))
      (node (ref "J28") (pin "2") (pinfunction "2_2") (pintype "passive"))
      (node (ref "J3") (pin "1") (pinfunction "1_1") (pintype "passive"))
      (node (ref "J4") (pin "2") (pinfunction "2_2") (pintype "passive"))
      (node (ref "J5") (pin "2") (pinfunction "2_2") (pintype "passive"))
      (node (ref "J6") (pin "1") (pinfunction "1_1") (pintype "passive"))
      (node (ref "J8") (pin "1") (pinfunction "1_1") (pintype "passive"))
      (node (ref "J9") (pin "3") (pinfunction "3_3") (pintype "passive"))
      (node (ref "Q1") (pin "3") (pinfunction "S_3") (pintype "passive"))
      (node (ref "Q2") (pin "2") (pinfunction "E_2") (pintype "passive"))
      (node (ref "Q3") (pin "2") (pinfunction "E_2") (pintype "passive"))
      (node (ref "Q9") (pin "2") (pinfunction "E_2") (pintype "passive"))
      (node (ref "R10") (pin "2") (pinfunction "2_2") (pintype "passive"))
      (node (ref "R12") (pin "2") (pinfunction "2_2") (pintype "passive"))
      (node (ref "R15") (pin "2") (pinfunction "2_2") (pintype "passive"))
      (node (ref "R2") (pin "2") (pinfunction "2_2") (pintype "passive"))
      (node (ref "R9") (pin "2") (pinfunction "2_2") (pintype "passive"))
      (node (ref "SW1") (pin "1") (pinfunction "1_1") (pintype "passive"))
      (node (ref "SW1") (pin "2") (pinfunction "2_2") (pintype "passive"))
      (node (ref "SW3") (pin "1") (pinfunction "1_1") (pintype "passive"))
      (node (ref "SW3") (pin "2") (pinfunction "2_2") (pintype "passive"))
      (node (ref "SW4") (pin "1") (pinfunction "1_1") (pintype "passive"))
      (node (ref "SW4") (pin "2") (pinfunction "2_2") (pintype "passive"))
      (node (ref "U1") (pin "2") (pinfunction "GND_2") (pintype "passive"))
      (node (ref "U2") (pin "2") (pinfunction "VSS_2") (pintype "passive"))
      (node (ref "U4") (pin "27") (pinfunction "GND_27") (pintype "passive"))
      (node (ref "U4") (pin "34") (pinfunction "GND_34") (pintype "passive"))
      (node (ref "U4") (pin "36") (pinfunction "GND_36") (pintype "passive"))
      (node (ref "U4") (pin "37") (pinfunction "GND_37") (pintype "passive"))
      (node (ref "U4") (pin "40") (pinfunction "GND_40") (pintype "passive"))
      (node (ref "U4") (pin "41") (pinfunction "GND_41") (pintype "passive"))
    )
    (net (code "38") (name "Net-(A3-Pad1)") (class "Default")
      (node (ref "A3") (pin "1") (pinfunction "1_1") (pintype "passive"))
      (node (ref "R6") (pin "1") (pinfunction "1_1") (pintype "passive"))
    )
    (net (code "39") (name "unconnected-(J18-Pad4)") (class "Default")
      (node (ref "J18") (pin "4") (pinfunction "4_4") (pintype "passive"))
    )
    (net (code "40") (name "unconnected-(J18-Pad8)") (class "Default")
      (node (ref "J18") (pin "8") (pinfunction "8_8") (pintype "passive"))
    )
    (net (code "41") (name "unconnected-(J18-Pad9)") (class "Default")
      (node (ref "J18") (pin "9") (pinfunction "9_9") (pintype "passive"))
    )
    (net (code "42") (name "unconnected-(J18-Pad10)") (class "Default")
      (node (ref "J18") (pin "10") (pinfunction "10_10") (pintype "passive"))
    )
    (net (code "43") (name "unconnected-(J18-Pad11)") (class "Default")
      (node (ref "J18") (pin "11") (pinfunction "11_11") (pintype "passive"))
    )
    (net (code "44") (name "unconnected-(J18-Pad12)") (class "Default")
      (node (ref "J18") (pin "12") (pinfunction "12_12") (pintype "passive"))
    )
    (net (code "45") (name "unconnected-(SW1-Pad3)") (class "Default")
      (node (ref "SW1") (pin "3") (pinfunction "3_3") (pintype "passive"))
    )
    (net (code "46") (name "unconnected-(SW4-Pad3)") (class "Default")
      (node (ref "SW4") (pin "3") (pinfunction "3_3") (pintype "passive"))
    )
    (net (code "47") (name "unconnected-(U4-ADC0-Pad9)") (class "Default")
      (node (ref "U4") (pin "9") (pinfunction "ADC0_9") (pintype "passive"))
    )
    (net (code "48") (name "unconnected-(U4-AVDD-Pad8)") (class "Default")
      (node (ref "U4") (pin "8") (pinfunction "AVDD_8") (pintype "passive"))
    )
    (net (code "49") (name "unconnected-(U4-DBG_RXD-Pad38)") (class "Default")
      (node (ref "U4") (pin "38") (pinfunction "DBG_RXD_38") (pintype "passive"))
    )
    (net (code "50") (name "unconnected-(U4-DBG_TXD-Pad39)") (class "Default")
      (node (ref "U4") (pin "39") (pinfunction "DBG_TXD_39") (pintype "passive"))
    )
    (net (code "51") (name "unconnected-(U4-RESERVED-Pad15)") (class "Default")
      (node (ref "U4") (pin "15") (pinfunction "RESERVED_15") (pintype "passive"))
    )
    (net (code "52") (name "unconnected-(U4-RFTXMON-Pad25)") (class "Default")
      (node (ref "U4") (pin "25") (pinfunction "RFTXMON_25") (pintype "passive"))
    )
    (net (code "53") (name "unconnected-(U4-RTS-Pad23)") (class "Default")
      (node (ref "U4") (pin "23") (pinfunction "RTS_23") (pintype "passive"))
    )
    (net (code "54") (name "unconnected-(U4-TXD_AUX-Pad29)") (class "Default")
      (node (ref "U4") (pin "29") (pinfunction "TXD_AUX_29") (pintype "passive"))
    )
    (net (code "55") (name "unconnected-(U4-VDD_EXT-Pad24)") (class "Default")
      (node (ref "U4") (pin "24") (pinfunction "VDD_EXT_24") (pintype "passive"))
    )
  )
)
